# PowerSupply.net
KiCad netlist of a schematic drawn in EAGLE
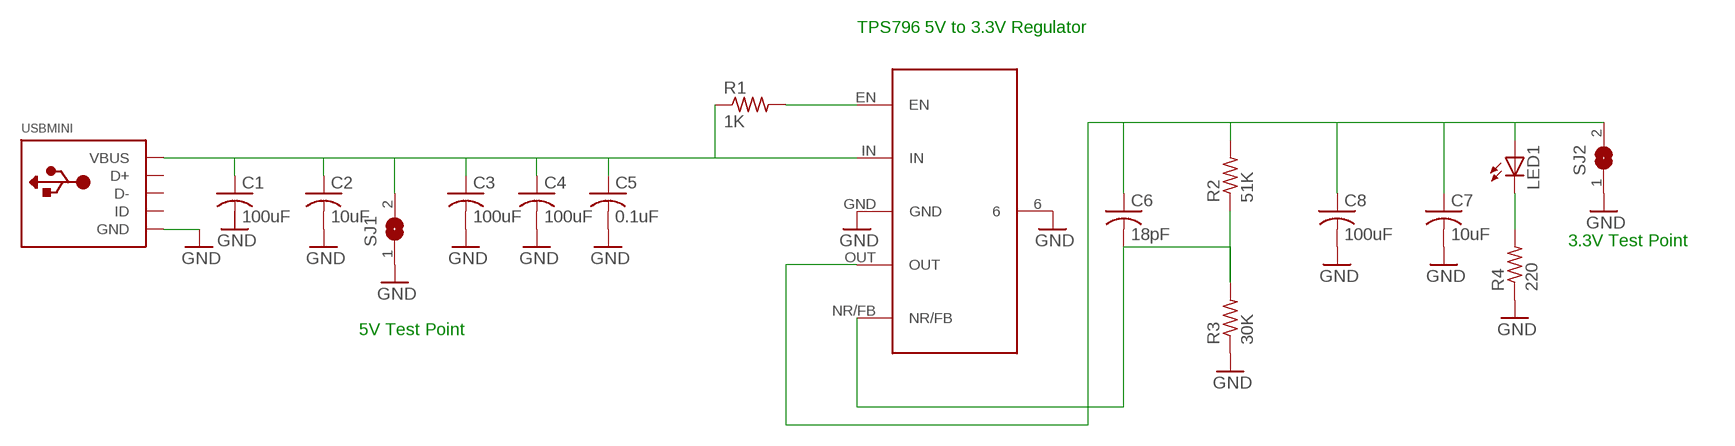
[diagram p0: schematic, sheet 1]

(export (version "E")
  (design (tool "Eeschema 10.0.6"))
  (components
    (comp (ref "C1")
      (value "100uF")
      (footprint "eagle-import:C1206K")
      (libsource (lib "eagle-import") (part "C-USC1206K"))
    )
    (comp (ref "C2")
      (value "10uF")
      (footprint "eagle-import:C1206K")
      (libsource (lib "eagle-import") (part "C-USC1206K"))
    )
    (comp (ref "C3")
      (value "100uF")
      (footprint "eagle-import:C1206K")
      (libsource (lib "eagle-import") (part "C-USC1206K"))
    )
    (comp (ref "C4")
      (value "100uF")
      (footprint "eagle-import:C1206K")
      (libsource (lib "eagle-import") (part "C-USC1206K"))
    )
    (comp (ref "C5")
      (value "0.1uF")
      (footprint "eagle-import:C1206K")
      (libsource (lib "eagle-import") (part "C-USC1206K"))
    )
    (comp (ref "C6")
      (value "18pF")
      (footprint "eagle-import:C1206K")
      (libsource (lib "eagle-import") (part "C-USC1206K"))
    )
    (comp (ref "C7")
      (value "10uF")
      (footprint "eagle-import:C1206K")
      (libsource (lib "eagle-import") (part "C-USC1206K"))
    )
    (comp (ref "C8")
      (value "100uF")
      (footprint "eagle-import:C1206K")
      (libsource (lib "eagle-import") (part "C-USC1206K"))
    )
    (comp (ref "LED1")
      (value "LEDCHIPLED_0805")
      (footprint "eagle-import:CHIPLED_0805")
      (libsource (lib "eagle-import") (part "LEDCHIPLED_0805"))
    )
    (comp (ref "R1")
      (value "1K")
      (footprint "eagle-import:R0805")
      (libsource (lib "eagle-import") (part "R-US_R0805"))
    )
    (comp (ref "R2")
      (value "51K")
      (footprint "eagle-import:R0805")
      (libsource (lib "eagle-import") (part "R-US_R0805"))
    )
    (comp (ref "R3")
      (value "30K")
      (footprint "eagle-import:R0805")
      (libsource (lib "eagle-import") (part "R-US_R0805"))
    )
    (comp (ref "R4")
      (value "220")
      (footprint "eagle-import:R0805")
      (libsource (lib "eagle-import") (part "R-US_R0805"))
    )
    (comp (ref "SJ1")
      (value "SJW")
      (footprint "eagle-import:SJW")
      (libsource (lib "eagle-import") (part "SJW"))
    )
    (comp (ref "SJ2")
      (value "SJW")
      (footprint "eagle-import:SJW")
      (libsource (lib "eagle-import") (part "SJW"))
    )
    (comp (ref "U$1")
      (value "TPS796")
      (footprint "eagle-import:TPS796")
      (libsource (lib "eagle-import") (part "TPS796"))
    )
    (comp (ref "USBMINI")
      (value "USBMINIB")
      (footprint "eagle-import:USB-MINIB")
      (libsource (lib "eagle-import") (part "USBMINIB"))
    )
  )
  (nets
    (net (code "1") (name "GND") (class "Default")
      (node (ref "C2") (pin "2") (pinfunction "2_2") (pintype "passive"))
      (node (ref "C3") (pin "2") (pinfunction "2_2") (pintype "passive"))
      (node (ref "C4") (pin "2") (pinfunction "2_2") (pintype "passive"))
      (node (ref "C5") (pin "2") (pinfunction "2_2") (pintype "passive"))
      (node (ref "C7") (pin "2") (pinfunction "2_2") (pintype "passive"))
      (node (ref "C8") (pin "2") (pinfunction "2_2") (pintype "passive"))
      (node (ref "R3") (pin "1") (pinfunction "1_1") (pintype "passive"))
      (node (ref "R4") (pin "1") (pinfunction "1_1") (pintype "passive"))
      (node (ref "SJ1") (pin "1") (pinfunction "1_1") (pintype "passive"))
      (node (ref "SJ2") (pin "1") (pinfunction "1_1") (pintype "passive"))
      (node (ref "U$1") (pin "6") (pinfunction "6_6") (pintype "bidirectional"))
      (node (ref "U$1") (pin "GND") (pinfunction "GND_GND") (pintype "bidirectional"))
      (node (ref "USBMINI") (pin "GND") (pinfunction "GND_GND") (pintype "power_in"))
    )
    (net (code "2") (name "Net-(C1-Pad1)") (class "Default")
      (node (ref "C1") (pin "1") (pinfunction "1_1") (pintype "passive"))
      (node (ref "C2") (pin "1") (pinfunction "1_1") (pintype "passive"))
      (node (ref "C3") (pin "1") (pinfunction "1_1") (pintype "passive"))
      (node (ref "C4") (pin "1") (pinfunction "1_1") (pintype "passive"))
      (node (ref "C5") (pin "1") (pinfunction "1_1") (pintype "passive"))
      (node (ref "R1") (pin "1") (pinfunction "1_1") (pintype "passive"))
      (node (ref "SJ1") (pin "2") (pinfunction "2_2") (pintype "passive"))
      (node (ref "U$1") (pin "IN") (pinfunction "IN_IN") (pintype "bidirectional"))
      (node (ref "USBMINI") (pin "VBUS") (pinfunction "VBUS_VBUS") (pintype "power_in"))
    )
    (net (code "3") (name "Net-(C6-Pad1)") (class "Default")
      (node (ref "C6") (pin "1") (pinfunction "1_1") (pintype "passive"))
      (node (ref "C7") (pin "1") (pinfunction "1_1") (pintype "passive"))
      (node (ref "C8") (pin "1") (pinfunction "1_1") (pintype "passive"))
      (node (ref "LED1") (pin "A") (pinfunction "A_A") (pintype "passive"))
      (node (ref "R2") (pin "2") (pinfunction "2_2") (pintype "passive"))
      (node (ref "SJ2") (pin "2") (pinfunction "2_2") (pintype "passive"))
      (node (ref "U$1") (pin "OUT") (pinfunction "OUT_OUT") (pintype "bidirectional"))
    )
    (net (code "4") (name "Net-(C6-Pad2)") (class "Default")
      (node (ref "C6") (pin "2") (pinfunction "2_2") (pintype "passive"))
      (node (ref "R2") (pin "1") (pinfunction "1_1") (pintype "passive"))
      (node (ref "R3") (pin "2") (pinfunction "2_2") (pintype "passive"))
      (node (ref "U$1") (pin "NR/FB") (pinfunction "NR/FB_NR/FB") (pintype "bidirectional"))
    )
    (net (code "5") (name "Net-(LED1-PadC)") (class "Default")
      (node (ref "LED1") (pin "C") (pinfunction "C_C") (pintype "passive"))
      (node (ref "R4") (pin "2") (pinfunction "2_2") (pintype "passive"))
    )
    (net (code "6") (name "Net-(R1-Pad2)") (class "Default")
      (node (ref "R1") (pin "2") (pinfunction "2_2") (pintype "passive"))
      (node (ref "U$1") (pin "EN") (pinfunction "EN_EN") (pintype "bidirectional"))
    )
    (net (code "7") (name "unconnected-(C1-Pad2)") (class "Default")
      (node (ref "C1") (pin "2") (pinfunction "2_2") (pintype "passive"))
    )
    (net (code "8") (name "unconnected-(USBMINI-PadD+)") (class "Default")
      (node (ref "USBMINI") (pin "D+") (pinfunction "D+_D+") (pintype "bidirectional"))
    )
    (net (code "9") (name "unconnected-(USBMINI-PadD-)") (class "Default")
      (node (ref "USBMINI") (pin "D-") (pinfunction "D-_D-") (pintype "bidirectional"))
    )
    (net (code "10") (name "unconnected-(USBMINI-PadID)") (class "Default")
      (node (ref "USBMINI") (pin "ID") (pinfunction "ID_ID") (pintype "bidirectional"))
    )
  )
)
